# Processor_Interface.net
KiCad netlist of a schematic drawn in Altium Designer
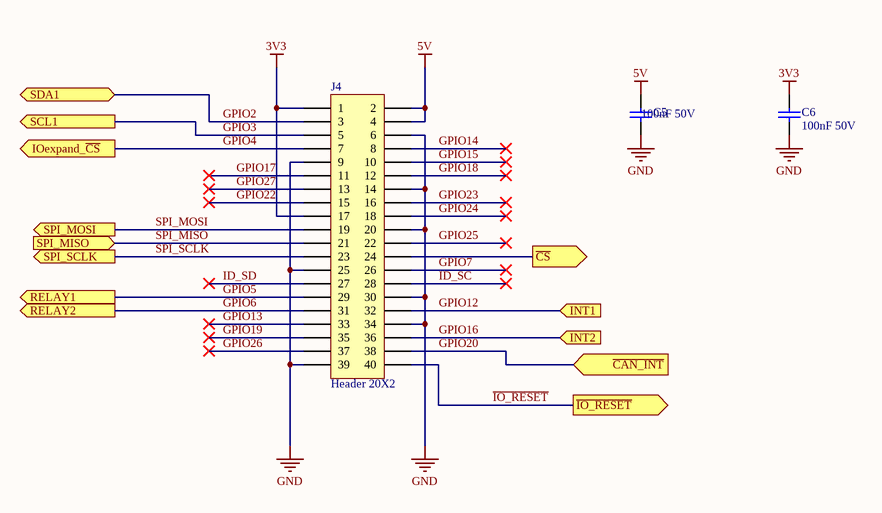
[diagram p0: Processor_Interface.SchDoc]

(export (version "E")
  (design (tool "Eeschema 10.0.6"))
  (components
    (comp (ref "C5")
      (value "100nF 50V")
      (footprint "0603C_L")
      (fields
        (field (name "MANUFACTURER") "Yageo")
        (field (name "MANUFACTURER PART NUMBER") "CC0603ZRY5V9BB104")
        (field (name "TOLERANCE") "-20%, +80%")
      )
      (libsource (lib "ICEdigikey") (part "Cap100nF_50V_0603"))
    )
    (comp (ref "C6")
      (value "100nF 50V")
      (footprint "0603C_L")
      (fields
        (field (name "MANUFACTURER") "Yageo")
        (field (name "MANUFACTURER PART NUMBER") "CC0603ZRY5V9BB104")
        (field (name "TOLERANCE") "-20%, +80%")
      )
      (libsource (lib "WCT") (part "Cap100nF_50V_0603"))
    )
    (comp (ref "J4")
      (value "Header 20X2")
      (footprint "HDR2X20")
      (description "Header, 20-Pin, Dual row")
      (fields (field (name "PUBLISHER") "Altium Limited"))
      (libsource (lib "Miscellaneous Connectors") (part "Header 20X2"))
    )
  )
  (nets
    (net (code "1") (name "/GPIO2") (class "Default")
      (node (ref "J4") (pin "3") (pinfunction "3_3") (pintype "passive"))
    )
    (net (code "2") (name "/GPIO3") (class "Default")
      (node (ref "J4") (pin "5") (pinfunction "5_5") (pintype "passive"))
    )
    (net (code "3") (name "/GPIO4") (class "Default")
      (node (ref "J4") (pin "7") (pinfunction "7_7") (pintype "passive"))
    )
    (net (code "4") (name "/GPIO5") (class "Default")
      (node (ref "J4") (pin "29") (pinfunction "29_29") (pintype "passive"))
    )
    (net (code "5") (name "/GPIO6") (class "Default")
      (node (ref "J4") (pin "31") (pinfunction "31_31") (pintype "passive"))
    )
    (net (code "6") (name "/GPIO7") (class "Default")
      (node (ref "J4") (pin "26") (pinfunction "26_26") (pintype "passive+no_connect"))
    )
    (net (code "7") (name "/GPIO12") (class "Default")
      (node (ref "J4") (pin "32") (pinfunction "32_32") (pintype "passive"))
    )
    (net (code "8") (name "/GPIO13") (class "Default")
      (node (ref "J4") (pin "33") (pinfunction "33_33") (pintype "passive+no_connect"))
    )
    (net (code "9") (name "/GPIO14") (class "Default")
      (node (ref "J4") (pin "8") (pinfunction "8_8") (pintype "passive+no_connect"))
    )
    (net (code "10") (name "/GPIO15") (class "Default")
      (node (ref "J4") (pin "10") (pinfunction "10_10") (pintype "passive+no_connect"))
    )
    (net (code "11") (name "/GPIO16") (class "Default")
      (node (ref "J4") (pin "36") (pinfunction "36_36") (pintype "passive"))
    )
    (net (code "12") (name "/GPIO17") (class "Default")
      (node (ref "J4") (pin "11") (pinfunction "11_11") (pintype "passive+no_connect"))
    )
    (net (code "13") (name "/GPIO18") (class "Default")
      (node (ref "J4") (pin "12") (pinfunction "12_12") (pintype "passive+no_connect"))
    )
    (net (code "14") (name "/GPIO19") (class "Default")
      (node (ref "J4") (pin "35") (pinfunction "35_35") (pintype "passive+no_connect"))
    )
    (net (code "15") (name "/GPIO20") (class "Default")
      (node (ref "J4") (pin "38") (pinfunction "38_38") (pintype "passive"))
    )
    (net (code "16") (name "/GPIO22") (class "Default")
      (node (ref "J4") (pin "15") (pinfunction "15_15") (pintype "passive+no_connect"))
    )
    (net (code "17") (name "/GPIO23") (class "Default")
      (node (ref "J4") (pin "16") (pinfunction "16_16") (pintype "passive+no_connect"))
    )
    (net (code "18") (name "/GPIO24") (class "Default")
      (node (ref "J4") (pin "18") (pinfunction "18_18") (pintype "passive+no_connect"))
    )
    (net (code "19") (name "/GPIO25") (class "Default")
      (node (ref "J4") (pin "22") (pinfunction "22_22") (pintype "passive+no_connect"))
    )
    (net (code "20") (name "/GPIO26") (class "Default")
      (node (ref "J4") (pin "37") (pinfunction "37_37") (pintype "passive+no_connect"))
    )
    (net (code "21") (name "/GPIO27") (class "Default")
      (node (ref "J4") (pin "13") (pinfunction "13_13") (pintype "passive+no_connect"))
    )
    (net (code "22") (name "/ID_SC") (class "Default")
      (node (ref "J4") (pin "28") (pinfunction "28_28") (pintype "passive+no_connect"))
    )
    (net (code "23") (name "/ID_SD") (class "Default")
      (node (ref "J4") (pin "27") (pinfunction "27_27") (pintype "passive+no_connect"))
    )
    (net (code "24") (name "/IO_RESET") (class "Default")
      (node (ref "J4") (pin "40") (pinfunction "40_40") (pintype "passive"))
    )
    (net (code "25") (name "/SPI_MISO") (class "Default")
      (node (ref "J4") (pin "21") (pinfunction "21_21") (pintype "passive"))
    )
    (net (code "26") (name "/SPI_MOSI") (class "Default")
      (node (ref "J4") (pin "19") (pinfunction "19_19") (pintype "passive"))
    )
    (net (code "27") (name "/SPI_SCLK") (class "Default")
      (node (ref "J4") (pin "23") (pinfunction "23_23") (pintype "passive"))
    )
    (net (code "28") (name "/~{CS}") (class "Default")
      (node (ref "J4") (pin "24") (pinfunction "24_24") (pintype "passive"))
    )
    (net (code "29") (name "3V3") (class "Default")
      (node (ref "C6") (pin "2") (pinfunction "2_2") (pintype "passive"))
      (node (ref "J4") (pin "1") (pinfunction "1_1") (pintype "passive"))
      (node (ref "J4") (pin "17") (pinfunction "17_17") (pintype "passive"))
    )
    (net (code "30") (name "5V") (class "Default")
      (node (ref "C5") (pin "2") (pinfunction "2_2") (pintype "passive"))
      (node (ref "J4") (pin "2") (pinfunction "2_2") (pintype "passive"))
      (node (ref "J4") (pin "4") (pinfunction "4_4") (pintype "passive"))
    )
    (net (code "31") (name "GND") (class "Default")
      (node (ref "C5") (pin "1") (pinfunction "1_1") (pintype "passive"))
      (node (ref "C6") (pin "1") (pinfunction "1_1") (pintype "passive"))
      (node (ref "J4") (pin "14") (pinfunction "14_14") (pintype "passive"))
      (node (ref "J4") (pin "20") (pinfunction "20_20") (pintype "passive"))
      (node (ref "J4") (pin "25") (pinfunction "25_25") (pintype "passive"))
      (node (ref "J4") (pin "30") (pinfunction "30_30") (pintype "passive"))
      (node (ref "J4") (pin "34") (pinfunction "34_34") (pintype "passive"))
      (node (ref "J4") (pin "39") (pinfunction "39_39") (pintype "passive"))
      (node (ref "J4") (pin "6") (pinfunction "6_6") (pintype "passive"))
      (node (ref "J4") (pin "9") (pinfunction "9_9") (pintype "passive"))
    )
  )
)
